# HVDCS_S3A6_48_TQFP.net
KiCad netlist of a schematic drawn in EAGLE
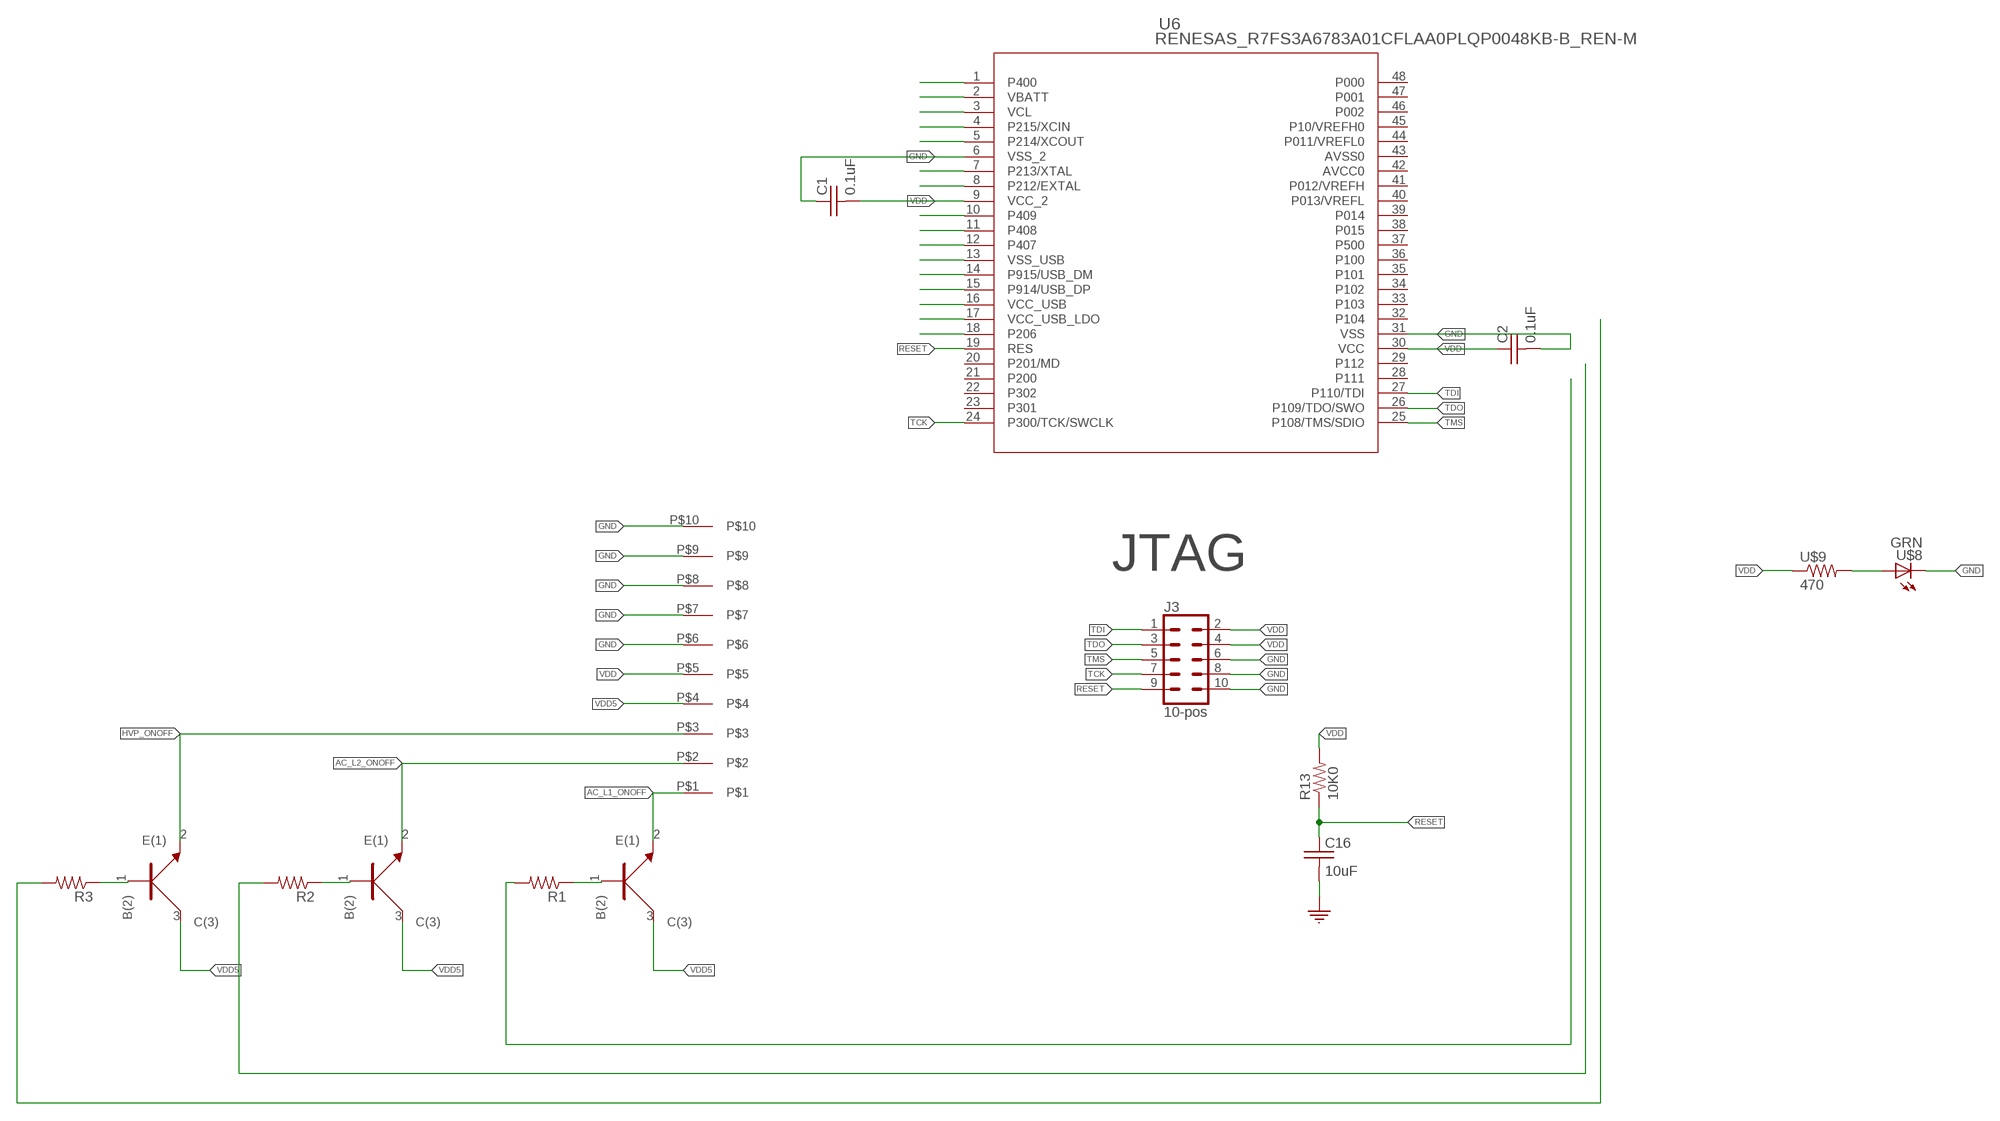
[diagram p0: schematic, sheet 1]

(export (version "E")
  (design (tool "Eeschema 10.0.6"))
  (components
    (comp (ref "C1")
      (value "0.1uF")
      (footprint "eagle-import:0402")
      (fields (field (name "PARTNO") "CL05F104ZO5NNNC"))
      (libsource (lib "eagle-import") (part "C_0402_0.1UF"))
    )
    (comp (ref "C2")
      (value "0.1uF")
      (footprint "eagle-import:0402")
      (fields (field (name "PARTNO") "CL05F104ZO5NNNC"))
      (libsource (lib "eagle-import") (part "C_0402_0.1UF"))
    )
    (comp (ref "C16")
      (value "10uF")
      (footprint "eagle-import:0402")
      (fields (field (name "PARTNO") "CL05A106MP8NUB8"))
      (libsource (lib "eagle-import") (part "C_0402_10UF"))
    )
    (comp (ref "J3")
      (value "10-pos")
      (footprint "eagle-import:2X5")
      (fields (field (name "PARTNO") "PH2RA-10-UA"))
      (libsource (lib "eagle-import") (part "CONN_05X2_RAPTH"))
    )
    (comp (ref "R1")
      (value "R_0402")
      (footprint "eagle-import:0402")
      (libsource (lib "eagle-import") (part "R_0402"))
    )
    (comp (ref "R2")
      (value "R_0402")
      (footprint "eagle-import:0402")
      (libsource (lib "eagle-import") (part "R_0402"))
    )
    (comp (ref "R3")
      (value "R_0402")
      (footprint "eagle-import:0402")
      (libsource (lib "eagle-import") (part "R_0402"))
    )
    (comp (ref "R13")
      (value "10K0")
      (footprint "eagle-import:0402")
      (fields (field (name "PARTNO") "RMCF0402JT10K0"))
      (libsource (lib "eagle-import") (part "R_0402_10K0"))
    )
    (comp (ref "U$5")
      (value "1_X_10_HEADER_GENERIC_.1INCH")
      (footprint "eagle-import:HEADER_1_X_10_.1_INCH")
      (libsource (lib "eagle-import") (part "1_X_10_HEADER_GENERIC_.1INCH"))
    )
    (comp (ref "U$8")
      (value "LED_0805_GREEN")
      (footprint "eagle-import:LED_0805_GREEN")
      (libsource (lib "eagle-import") (part "LED_0805_GREEN"))
    )
    (comp (ref "U$9")
      (value "R_0805_470")
      (footprint "eagle-import:R_0805_470")
      (libsource (lib "eagle-import") (part "R_0805_470"))
    )
    (comp (ref "U1")
      (value "NPN")
      (footprint "eagle-import:SOT323")
      (fields (field (name "PARTNO") "BC846BW_NPN"))
      (libsource (lib "eagle-import") (part "BC846BW"))
    )
    (comp (ref "U2")
      (value "NPN")
      (footprint "eagle-import:SOT323")
      (fields (field (name "PARTNO") "BC846BW_NPN"))
      (libsource (lib "eagle-import") (part "BC846BW"))
    )
    (comp (ref "U3")
      (value "NPN")
      (footprint "eagle-import:SOT323")
      (fields (field (name "PARTNO") "BC846BW_NPN"))
      (libsource (lib "eagle-import") (part "BC846BW"))
    )
    (comp (ref "U6")
      (value "RENESAS_R7FS3A6783A01CFLAA0PLQP0048KB-B_REN-M")
      (footprint "eagle-import:PLQP0048KB-B_REN-M")
      (fields
        (field (name "MANUFACTURER_PART_NUMBER") "R7FS3A6783A01CFL#AA0")
        (field (name "COPYRIGHT") "Copyright (C) 2021 Accelerated Designs. All rights reserved")
      )
      (libsource (lib "eagle-import") (part "RENESAS_R7FS3A6783A01CFLAA0PLQP0048KB-B_REN-M"))
    )
  )
  (nets
    (net (code "1") (name "/AVCC0") (class "Default")
      (node (ref "U6") (pin "42") (pinfunction "AVCC0_42") (pintype "power_in"))
    )
    (net (code "2") (name "/P10{slash}VREFH0") (class "Default")
      (node (ref "U6") (pin "45") (pinfunction "P10/VREFH0_45") (pintype "power_in"))
    )
    (net (code "3") (name "/P011{slash}VREFL0") (class "Default")
      (node (ref "U6") (pin "44") (pinfunction "P011/VREFL0_44") (pintype "power_in"))
    )
    (net (code "4") (name "/P012{slash}VREFH") (class "Default")
      (node (ref "U6") (pin "41") (pinfunction "P012/VREFH_41") (pintype "power_in"))
    )
    (net (code "5") (name "/P013{slash}VREFL") (class "Default")
      (node (ref "U6") (pin "40") (pinfunction "P013/VREFL_40") (pintype "power_in"))
    )
    (net (code "6") (name "AC_L1_ONOFF") (class "Default")
      (node (ref "U$5") (pin "P$1") (pinfunction "P$1_P$1") (pintype "bidirectional"))
      (node (ref "U1") (pin "2") (pinfunction "E(1)_2") (pintype "output"))
    )
    (net (code "7") (name "AC_L2_ONOFF") (class "Default")
      (node (ref "U$5") (pin "P$2") (pinfunction "P$2_P$2") (pintype "bidirectional"))
      (node (ref "U2") (pin "2") (pinfunction "E(1)_2") (pintype "output"))
    )
    (net (code "8") (name "GND") (class "Default")
      (node (ref "C1") (pin "P$1") (pinfunction "1_P$1") (pintype "passive"))
      (node (ref "C16") (pin "P$2") (pinfunction "2_P$2") (pintype "passive"))
      (node (ref "C2") (pin "P$2") (pinfunction "2_P$2") (pintype "passive"))
      (node (ref "J3") (pin "10") (pinfunction "10_10") (pintype "passive"))
      (node (ref "J3") (pin "6") (pinfunction "6_6") (pintype "passive"))
      (node (ref "J3") (pin "8") (pinfunction "8_8") (pintype "passive"))
      (node (ref "U$5") (pin "P$10") (pinfunction "P$10_P$10") (pintype "bidirectional"))
      (node (ref "U$5") (pin "P$6") (pinfunction "P$6_P$6") (pintype "bidirectional"))
      (node (ref "U$5") (pin "P$7") (pinfunction "P$7_P$7") (pintype "bidirectional"))
      (node (ref "U$5") (pin "P$8") (pinfunction "P$8_P$8") (pintype "bidirectional"))
      (node (ref "U$5") (pin "P$9") (pinfunction "P$9_P$9") (pintype "bidirectional"))
      (node (ref "U$8") (pin "C") (pinfunction "C_C") (pintype "passive"))
      (node (ref "U6") (pin "31") (pinfunction "VSS_31") (pintype "passive"))
      (node (ref "U6") (pin "6") (pinfunction "VSS_2_6") (pintype "passive"))
    )
    (net (code "9") (name "HVP_ONOFF") (class "Default")
      (node (ref "U$5") (pin "P$3") (pinfunction "P$3_P$3") (pintype "bidirectional"))
      (node (ref "U3") (pin "2") (pinfunction "E(1)_2") (pintype "output"))
    )
    (net (code "10") (name "Net-(R1-1)") (class "Default")
      (node (ref "R1") (pin "P$1") (pinfunction "1_P$1") (pintype "passive"))
      (node (ref "U1") (pin "1") (pinfunction "B(2)_1") (pintype "input"))
    )
    (net (code "11") (name "Net-(R2-1)") (class "Default")
      (node (ref "R2") (pin "P$1") (pinfunction "1_P$1") (pintype "passive"))
      (node (ref "U2") (pin "1") (pinfunction "B(2)_1") (pintype "input"))
    )
    (net (code "12") (name "Net-(R3-1)") (class "Default")
      (node (ref "R3") (pin "P$1") (pinfunction "1_P$1") (pintype "passive"))
      (node (ref "U3") (pin "1") (pinfunction "B(2)_1") (pintype "input"))
    )
    (net (code "13") (name "Net-(U$8-PadA)") (class "Default")
      (node (ref "U$8") (pin "A") (pinfunction "A_A") (pintype "passive"))
      (node (ref "U$9") (pin "2") (pinfunction "2_2") (pintype "passive"))
    )
    (net (code "14") (name "RESET") (class "Default")
      (node (ref "C16") (pin "P$1") (pinfunction "1_P$1") (pintype "passive"))
      (node (ref "J3") (pin "9") (pinfunction "9_9") (pintype "passive"))
      (node (ref "R13") (pin "P$1") (pinfunction "1_P$1") (pintype "passive"))
      (node (ref "U6") (pin "19") (pinfunction "RES_19") (pintype "passive"))
    )
    (net (code "15") (name "TCK") (class "Default")
      (node (ref "J3") (pin "7") (pinfunction "7_7") (pintype "passive"))
      (node (ref "U6") (pin "24") (pinfunction "P300/TCK/SWCLK_24") (pintype "bidirectional"))
    )
    (net (code "16") (name "TDI") (class "Default")
      (node (ref "J3") (pin "1") (pinfunction "1_1") (pintype "passive"))
      (node (ref "U6") (pin "27") (pinfunction "P110/TDI_27") (pintype "bidirectional"))
    )
    (net (code "17") (name "TDO") (class "Default")
      (node (ref "J3") (pin "3") (pinfunction "3_3") (pintype "passive"))
      (node (ref "U6") (pin "26") (pinfunction "P109/TDO/SWO_26") (pintype "bidirectional"))
    )
    (net (code "18") (name "TMS") (class "Default")
      (node (ref "J3") (pin "5") (pinfunction "5_5") (pintype "passive"))
      (node (ref "U6") (pin "25") (pinfunction "P108/TMS/SDIO_25") (pintype "bidirectional"))
    )
    (net (code "19") (name "VDD") (class "Default")
      (node (ref "C1") (pin "P$2") (pinfunction "2_P$2") (pintype "passive"))
      (node (ref "C2") (pin "P$1") (pinfunction "1_P$1") (pintype "passive"))
      (node (ref "J3") (pin "2") (pinfunction "2_2") (pintype "passive"))
      (node (ref "J3") (pin "4") (pinfunction "4_4") (pintype "passive"))
      (node (ref "R13") (pin "P$2") (pinfunction "2_P$2") (pintype "passive"))
      (node (ref "U$5") (pin "P$5") (pinfunction "P$5_P$5") (pintype "bidirectional"))
      (node (ref "U$9") (pin "1") (pinfunction "1_1") (pintype "passive"))
      (node (ref "U6") (pin "30") (pinfunction "VCC_30") (pintype "power_in"))
      (node (ref "U6") (pin "9") (pinfunction "VCC_2_9") (pintype "power_in"))
    )
    (net (code "20") (name "VDD5") (class "Default")
      (node (ref "U$5") (pin "P$4") (pinfunction "P$4_P$4") (pintype "bidirectional"))
      (node (ref "U1") (pin "3") (pinfunction "C(3)_3") (pintype "input"))
      (node (ref "U2") (pin "3") (pinfunction "C(3)_3") (pintype "input"))
      (node (ref "U3") (pin "3") (pinfunction "C(3)_3") (pintype "input"))
    )
    (net (code "21") (name "unconnected-(R1-2-PadP$2)") (class "Default")
      (node (ref "R1") (pin "P$2") (pinfunction "2_P$2") (pintype "passive"))
    )
    (net (code "22") (name "unconnected-(R2-2-PadP$2)") (class "Default")
      (node (ref "R2") (pin "P$2") (pinfunction "2_P$2") (pintype "passive"))
    )
    (net (code "23") (name "unconnected-(R3-2-PadP$2)") (class "Default")
      (node (ref "R3") (pin "P$2") (pinfunction "2_P$2") (pintype "passive"))
    )
    (net (code "24") (name "unconnected-(U6-AVSS0-Pad43)") (class "Default")
      (node (ref "U6") (pin "43") (pinfunction "AVSS0_43") (pintype "passive"))
    )
    (net (code "25") (name "unconnected-(U6-P000-Pad48)") (class "Default")
      (node (ref "U6") (pin "48") (pinfunction "P000_48") (pintype "bidirectional"))
    )
    (net (code "26") (name "unconnected-(U6-P001-Pad47)") (class "Default")
      (node (ref "U6") (pin "47") (pinfunction "P001_47") (pintype "bidirectional"))
    )
    (net (code "27") (name "unconnected-(U6-P002-Pad46)") (class "Default")
      (node (ref "U6") (pin "46") (pinfunction "P002_46") (pintype "bidirectional"))
    )
    (net (code "28") (name "unconnected-(U6-P014-Pad39)") (class "Default")
      (node (ref "U6") (pin "39") (pinfunction "P014_39") (pintype "bidirectional"))
    )
    (net (code "29") (name "unconnected-(U6-P015-Pad38)") (class "Default")
      (node (ref "U6") (pin "38") (pinfunction "P015_38") (pintype "bidirectional"))
    )
    (net (code "30") (name "unconnected-(U6-P100-Pad36)") (class "Default")
      (node (ref "U6") (pin "36") (pinfunction "P100_36") (pintype "bidirectional"))
    )
    (net (code "31") (name "unconnected-(U6-P101-Pad35)") (class "Default")
      (node (ref "U6") (pin "35") (pinfunction "P101_35") (pintype "bidirectional"))
    )
    (net (code "32") (name "unconnected-(U6-P102-Pad34)") (class "Default")
      (node (ref "U6") (pin "34") (pinfunction "P102_34") (pintype "bidirectional"))
    )
    (net (code "33") (name "unconnected-(U6-P103-Pad33)") (class "Default")
      (node (ref "U6") (pin "33") (pinfunction "P103_33") (pintype "bidirectional"))
    )
    (net (code "34") (name "unconnected-(U6-P104-Pad32)") (class "Default")
      (node (ref "U6") (pin "32") (pinfunction "P104_32") (pintype "bidirectional"))
    )
    (net (code "35") (name "unconnected-(U6-P111-Pad28)") (class "Default")
      (node (ref "U6") (pin "28") (pinfunction "P111_28") (pintype "bidirectional"))
    )
    (net (code "36") (name "unconnected-(U6-P112-Pad29)") (class "Default")
      (node (ref "U6") (pin "29") (pinfunction "P112_29") (pintype "bidirectional"))
    )
    (net (code "37") (name "unconnected-(U6-P200-Pad21)") (class "Default")
      (node (ref "U6") (pin "21") (pinfunction "P200_21") (pintype "bidirectional"))
    )
    (net (code "38") (name "unconnected-(U6-P201{slash}MD-Pad20)") (class "Default")
      (node (ref "U6") (pin "20") (pinfunction "P201/MD_20") (pintype "bidirectional"))
    )
    (net (code "39") (name "unconnected-(U6-P206-Pad18)") (class "Default")
      (node (ref "U6") (pin "18") (pinfunction "P206_18") (pintype "bidirectional"))
    )
    (net (code "40") (name "unconnected-(U6-P212{slash}EXTAL-Pad8)") (class "Default")
      (node (ref "U6") (pin "8") (pinfunction "P212/EXTAL_8") (pintype "bidirectional"))
    )
    (net (code "41") (name "unconnected-(U6-P213{slash}XTAL-Pad7)") (class "Default")
      (node (ref "U6") (pin "7") (pinfunction "P213/XTAL_7") (pintype "bidirectional"))
    )
    (net (code "42") (name "unconnected-(U6-P214{slash}XCOUT-Pad5)") (class "Default")
      (node (ref "U6") (pin "5") (pinfunction "P214/XCOUT_5") (pintype "output"))
    )
    (net (code "43") (name "unconnected-(U6-P215{slash}XCIN-Pad4)") (class "Default")
      (node (ref "U6") (pin "4") (pinfunction "P215/XCIN_4") (pintype "bidirectional"))
    )
    (net (code "44") (name "unconnected-(U6-P301-Pad23)") (class "Default")
      (node (ref "U6") (pin "23") (pinfunction "P301_23") (pintype "bidirectional"))
    )
    (net (code "45") (name "unconnected-(U6-P302-Pad22)") (class "Default")
      (node (ref "U6") (pin "22") (pinfunction "P302_22") (pintype "bidirectional"))
    )
    (net (code "46") (name "unconnected-(U6-P400-Pad1)") (class "Default")
      (node (ref "U6") (pin "1") (pinfunction "P400_1") (pintype "bidirectional"))
    )
    (net (code "47") (name "unconnected-(U6-P407-Pad12)") (class "Default")
      (node (ref "U6") (pin "12") (pinfunction "P407_12") (pintype "bidirectional"))
    )
    (net (code "48") (name "unconnected-(U6-P408-Pad11)") (class "Default")
      (node (ref "U6") (pin "11") (pinfunction "P408_11") (pintype "bidirectional"))
    )
    (net (code "49") (name "unconnected-(U6-P409-Pad10)") (class "Default")
      (node (ref "U6") (pin "10") (pinfunction "P409_10") (pintype "bidirectional"))
    )
    (net (code "50") (name "unconnected-(U6-P500-Pad37)") (class "Default")
      (node (ref "U6") (pin "37") (pinfunction "P500_37") (pintype "bidirectional"))
    )
    (net (code "51") (name "unconnected-(U6-P914{slash}USB_DP-Pad15)") (class "Default")
      (node (ref "U6") (pin "15") (pinfunction "P914/USB_DP_15") (pintype "bidirectional"))
    )
    (net (code "52") (name "unconnected-(U6-P915{slash}USB_DM-Pad14)") (class "Default")
      (node (ref "U6") (pin "14") (pinfunction "P915/USB_DM_14") (pintype "bidirectional"))
    )
    (net (code "53") (name "unconnected-(U6-VBATT-Pad2)") (class "Default")
      (node (ref "U6") (pin "2") (pinfunction "VBATT_2") (pintype "passive"))
    )
    (net (code "54") (name "unconnected-(U6-VCC_USB-Pad16)") (class "Default")
      (node (ref "U6") (pin "16") (pinfunction "VCC_USB_16") (pintype "power_in"))
    )
    (net (code "55") (name "unconnected-(U6-VCC_USB_LDO-Pad17)") (class "Default")
      (node (ref "U6") (pin "17") (pinfunction "VCC_USB_LDO_17") (pintype "power_in"))
    )
    (net (code "56") (name "unconnected-(U6-VCL-Pad3)") (class "Default")
      (node (ref "U6") (pin "3") (pinfunction "VCL_3") (pintype "passive"))
    )
    (net (code "57") (name "unconnected-(U6-VSS_USB-Pad13)") (class "Default")
      (node (ref "U6") (pin "13") (pinfunction "VSS_USB_13") (pintype "passive"))
    )
  )
)
